# main1.net
KiCad netlist of a schematic drawn in EAGLE
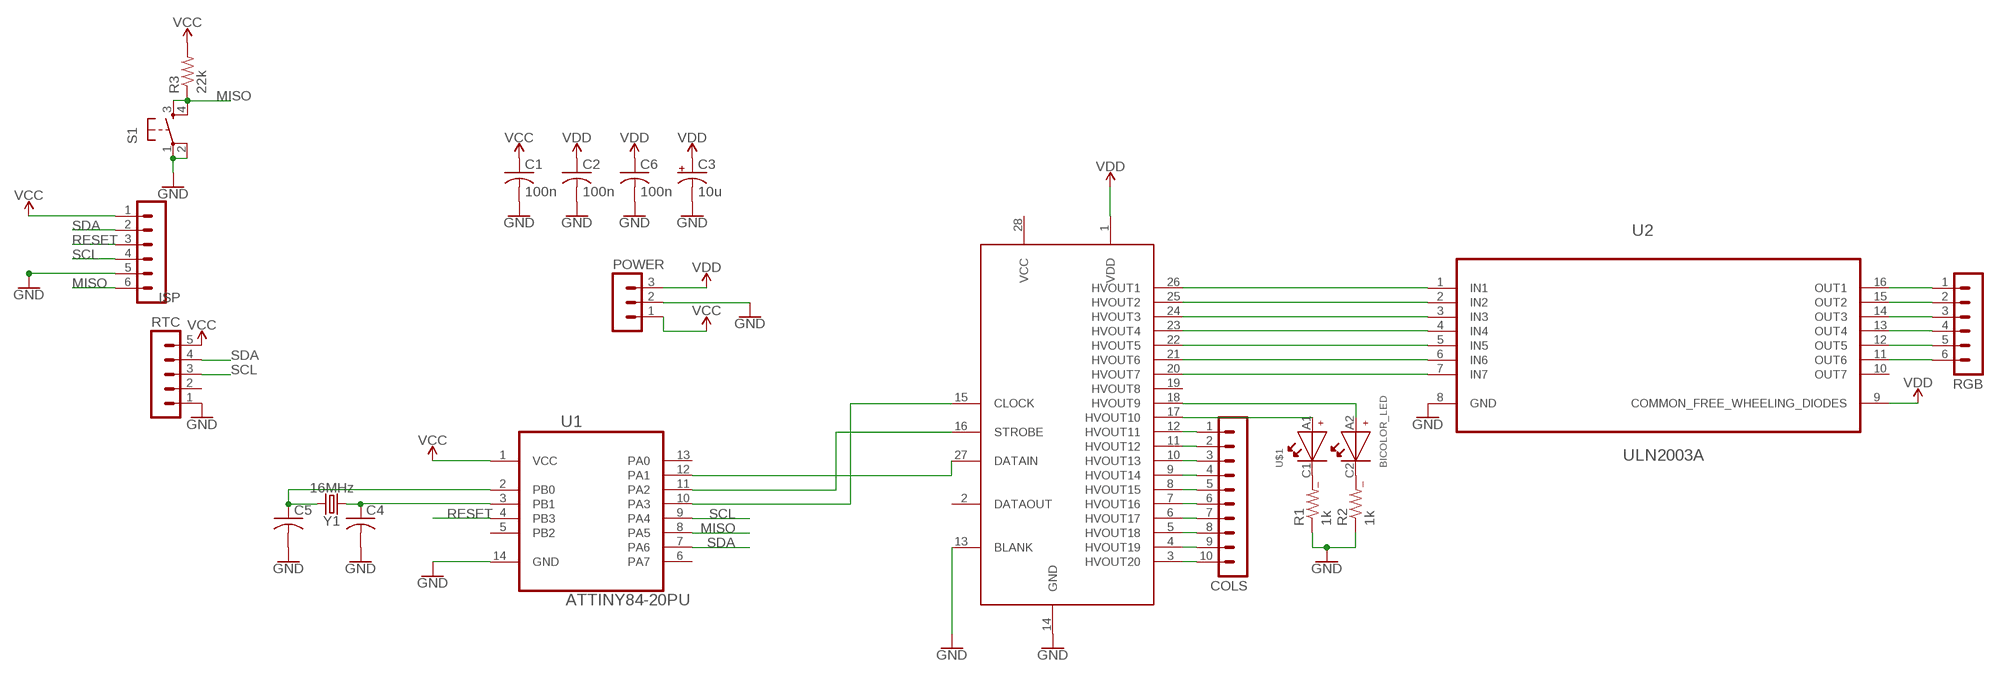
[diagram p0: schematic, sheet 1]

(export (version "E")
  (design (tool "Eeschema 10.0.6"))
  (components
    (comp (ref "C1")
      (value "100n")
      (footprint "eagle-import:C025-025X050")
      (libsource (lib "eagle-import") (part "C-US025-025X050"))
    )
    (comp (ref "C2")
      (value "100n")
      (footprint "eagle-import:C025-025X050")
      (libsource (lib "eagle-import") (part "C-US025-025X050"))
    )
    (comp (ref "C3")
      (value "10u")
      (footprint "eagle-import:E2-5")
      (libsource (lib "eagle-import") (part "CPOL-USE2-5"))
    )
    (comp (ref "C4")
      (value "C-USC0603K")
      (footprint "eagle-import:C0603K")
      (libsource (lib "eagle-import") (part "C-USC0603K"))
    )
    (comp (ref "C5")
      (value "C-USC0603K")
      (footprint "eagle-import:C0603K")
      (libsource (lib "eagle-import") (part "C-USC0603K"))
    )
    (comp (ref "C6")
      (value "100n")
      (footprint "eagle-import:C025-025X050")
      (libsource (lib "eagle-import") (part "C-US025-025X050"))
    )
    (comp (ref "COLS")
      (value "MA10-1W")
      (footprint "eagle-import:MA10-1W")
      (libsource (lib "eagle-import") (part "MA10-1W"))
    )
    (comp (ref "ISP")
      (value "MA06-1")
      (footprint "eagle-import:MA06-1")
      (libsource (lib "eagle-import") (part "MA06-1"))
    )
    (comp (ref "POWER")
      (value "MA03-1")
      (footprint "eagle-import:MA03-1")
      (libsource (lib "eagle-import") (part "MA03-1"))
    )
    (comp (ref "R1")
      (value "1k")
      (footprint "eagle-import:R0603")
      (libsource (lib "eagle-import") (part "R-US_R0603"))
    )
    (comp (ref "R2")
      (value "1k")
      (footprint "eagle-import:R0603")
      (libsource (lib "eagle-import") (part "R-US_R0603"))
    )
    (comp (ref "R3")
      (value "22k")
      (footprint "eagle-import:R0603")
      (libsource (lib "eagle-import") (part "R-US_R0603"))
    )
    (comp (ref "RGB")
      (value "MA06-1")
      (footprint "eagle-import:MA06-1")
      (libsource (lib "eagle-import") (part "MA06-1"))
    )
    (comp (ref "RTC")
      (value "MA05-1")
      (footprint "eagle-import:MA05-1")
      (libsource (lib "eagle-import") (part "MA05-1"))
    )
    (comp (ref "S1")
      (value "TAC_SWITCHPTH")
      (footprint "eagle-import:TACTILE-PTH")
      (libsource (lib "eagle-import") (part "TAC_SWITCHPTH"))
    )
    (comp (ref "U$1")
      (value "BICOLOR_LED")
      (footprint "eagle-import:BICOLOR_LED")
      (libsource (lib "eagle-import") (part "BICOLOR_LED"))
    )
    (comp (ref "U$2")
      (value "HV5812")
      (footprint "eagle-import:DIP254P1524X482-28")
      (libsource (lib "eagle-import") (part "HV5812"))
    )
    (comp (ref "U1")
      (value "ATTINY84-20PU")
      (footprint "eagle-import:DIP254P762X533-14")
      (libsource (lib "eagle-import") (part "ATTINY84-20PU"))
    )
    (comp (ref "U2")
      (value "ULN2003A")
      (footprint "eagle-import:DIP254P762X508-16")
      (libsource (lib "eagle-import") (part "ULN2003A"))
    )
    (comp (ref "Y1")
      (value "16MHz")
      (footprint "eagle-import:HC49US")
      (libsource (lib "eagle-import") (part "CRYSTAL-16MHZPTH-HC49US"))
    )
  )
  (nets
    (net (code "1") (name "/MISO") (class "Default")
      (node (ref "ISP") (pin "6") (pinfunction "6_6") (pintype "passive"))
      (node (ref "R3") (pin "1") (pinfunction "1_1") (pintype "passive"))
      (node (ref "S1") (pin "3") (pinfunction "3_3") (pintype "passive"))
      (node (ref "S1") (pin "4") (pinfunction "4_4") (pintype "passive"))
      (node (ref "U1") (pin "8") (pinfunction "PA5_8") (pintype "bidirectional"))
    )
    (net (code "2") (name "/RESET") (class "Default")
      (node (ref "ISP") (pin "3") (pinfunction "3_3") (pintype "passive"))
      (node (ref "U1") (pin "4") (pinfunction "PB3_4") (pintype "bidirectional"))
    )
    (net (code "3") (name "/SCL") (class "Default")
      (node (ref "ISP") (pin "4") (pinfunction "4_4") (pintype "passive"))
      (node (ref "RTC") (pin "3") (pinfunction "3_3") (pintype "passive"))
      (node (ref "U1") (pin "9") (pinfunction "PA4_9") (pintype "bidirectional"))
    )
    (net (code "4") (name "/SDA") (class "Default")
      (node (ref "ISP") (pin "2") (pinfunction "2_2") (pintype "passive"))
      (node (ref "RTC") (pin "4") (pinfunction "4_4") (pintype "passive"))
      (node (ref "U1") (pin "7") (pinfunction "PA6_7") (pintype "bidirectional"))
    )
    (net (code "5") (name "GND") (class "Default")
      (node (ref "C1") (pin "2") (pinfunction "2_2") (pintype "passive"))
      (node (ref "C2") (pin "2") (pinfunction "2_2") (pintype "passive"))
      (node (ref "C3") (pin "-") (pinfunction "-_-") (pintype "passive"))
      (node (ref "C4") (pin "2") (pinfunction "2_2") (pintype "passive"))
      (node (ref "C5") (pin "2") (pinfunction "2_2") (pintype "passive"))
      (node (ref "C6") (pin "2") (pinfunction "2_2") (pintype "passive"))
      (node (ref "ISP") (pin "5") (pinfunction "5_5") (pintype "passive"))
      (node (ref "POWER") (pin "2") (pinfunction "2_2") (pintype "passive"))
      (node (ref "R1") (pin "1") (pinfunction "1_1") (pintype "passive"))
      (node (ref "R2") (pin "1") (pinfunction "1_1") (pintype "passive"))
      (node (ref "RTC") (pin "1") (pinfunction "1_1") (pintype "passive"))
      (node (ref "S1") (pin "1") (pinfunction "1_1") (pintype "passive"))
      (node (ref "S1") (pin "2") (pinfunction "2_2") (pintype "passive"))
      (node (ref "U$2") (pin "13") (pinfunction "BLANK_13") (pintype "bidirectional"))
      (node (ref "U$2") (pin "14") (pinfunction "GND_14") (pintype "bidirectional"))
      (node (ref "U1") (pin "14") (pinfunction "GND_14") (pintype "passive"))
      (node (ref "U2") (pin "8") (pinfunction "GND_8") (pintype "passive"))
    )
    (net (code "6") (name "Net-(R1-Pad2)") (class "Default")
      (node (ref "R1") (pin "2") (pinfunction "2_2") (pintype "passive"))
      (node (ref "U$1") (pin "C1") (pinfunction "C1_C1") (pintype "passive"))
    )
    (net (code "7") (name "Net-(R2-Pad2)") (class "Default")
      (node (ref "R2") (pin "2") (pinfunction "2_2") (pintype "passive"))
      (node (ref "U$1") (pin "C2") (pinfunction "C2_C2") (pintype "passive"))
    )
    (net (code "8") (name "Net-(U$2-CLOCK)") (class "Default")
      (node (ref "U$2") (pin "15") (pinfunction "CLOCK_15") (pintype "bidirectional"))
      (node (ref "U1") (pin "10") (pinfunction "PA3_10") (pintype "bidirectional"))
    )
    (net (code "9") (name "Net-(U$2-DATAIN)") (class "Default")
      (node (ref "U$2") (pin "27") (pinfunction "DATAIN_27") (pintype "bidirectional"))
      (node (ref "U1") (pin "12") (pinfunction "PA1_12") (pintype "bidirectional"))
    )
    (net (code "10") (name "Net-(U$2-HVOUT1)") (class "Default")
      (node (ref "U$2") (pin "26") (pinfunction "HVOUT1_26") (pintype "bidirectional"))
      (node (ref "U2") (pin "1") (pinfunction "IN1_1") (pintype "input"))
    )
    (net (code "11") (name "Net-(U$2-HVOUT2)") (class "Default")
      (node (ref "U$2") (pin "25") (pinfunction "HVOUT2_25") (pintype "bidirectional"))
      (node (ref "U2") (pin "2") (pinfunction "IN2_2") (pintype "input"))
    )
    (net (code "12") (name "Net-(U$2-HVOUT3)") (class "Default")
      (node (ref "U$2") (pin "24") (pinfunction "HVOUT3_24") (pintype "bidirectional"))
      (node (ref "U2") (pin "3") (pinfunction "IN3_3") (pintype "input"))
    )
    (net (code "13") (name "Net-(U$2-HVOUT4)") (class "Default")
      (node (ref "U$2") (pin "23") (pinfunction "HVOUT4_23") (pintype "bidirectional"))
      (node (ref "U2") (pin "4") (pinfunction "IN4_4") (pintype "input"))
    )
    (net (code "14") (name "Net-(U$2-HVOUT5)") (class "Default")
      (node (ref "U$2") (pin "22") (pinfunction "HVOUT5_22") (pintype "bidirectional"))
      (node (ref "U2") (pin "5") (pinfunction "IN5_5") (pintype "input"))
    )
    (net (code "15") (name "Net-(U$2-HVOUT6)") (class "Default")
      (node (ref "U$2") (pin "21") (pinfunction "HVOUT6_21") (pintype "bidirectional"))
      (node (ref "U2") (pin "6") (pinfunction "IN6_6") (pintype "input"))
    )
    (net (code "16") (name "Net-(U$2-HVOUT7)") (class "Default")
      (node (ref "U$2") (pin "20") (pinfunction "HVOUT7_20") (pintype "bidirectional"))
      (node (ref "U2") (pin "7") (pinfunction "IN7_7") (pintype "input"))
    )
    (net (code "17") (name "Net-(U$2-HVOUT9)") (class "Default")
      (node (ref "U$1") (pin "A2") (pinfunction "A2_A2") (pintype "passive"))
      (node (ref "U$2") (pin "18") (pinfunction "HVOUT9_18") (pintype "bidirectional"))
    )
    (net (code "18") (name "Net-(U$2-HVOUT10)") (class "Default")
      (node (ref "U$1") (pin "A1") (pinfunction "A1_A1") (pintype "passive"))
      (node (ref "U$2") (pin "17") (pinfunction "HVOUT10_17") (pintype "bidirectional"))
    )
    (net (code "19") (name "Net-(U$2-HVOUT11)") (class "Default")
      (node (ref "COLS") (pin "1") (pinfunction "1_1") (pintype "passive"))
      (node (ref "U$2") (pin "12") (pinfunction "HVOUT11_12") (pintype "bidirectional"))
    )
    (net (code "20") (name "Net-(U$2-HVOUT12)") (class "Default")
      (node (ref "COLS") (pin "2") (pinfunction "2_2") (pintype "passive"))
      (node (ref "U$2") (pin "11") (pinfunction "HVOUT12_11") (pintype "bidirectional"))
    )
    (net (code "21") (name "Net-(U$2-HVOUT13)") (class "Default")
      (node (ref "COLS") (pin "3") (pinfunction "3_3") (pintype "passive"))
      (node (ref "U$2") (pin "10") (pinfunction "HVOUT13_10") (pintype "bidirectional"))
    )
    (net (code "22") (name "Net-(U$2-HVOUT14)") (class "Default")
      (node (ref "COLS") (pin "4") (pinfunction "4_4") (pintype "passive"))
      (node (ref "U$2") (pin "9") (pinfunction "HVOUT14_9") (pintype "bidirectional"))
    )
    (net (code "23") (name "Net-(U$2-HVOUT15)") (class "Default")
      (node (ref "COLS") (pin "5") (pinfunction "5_5") (pintype "passive"))
      (node (ref "U$2") (pin "8") (pinfunction "HVOUT15_8") (pintype "bidirectional"))
    )
    (net (code "24") (name "Net-(U$2-HVOUT16)") (class "Default")
      (node (ref "COLS") (pin "6") (pinfunction "6_6") (pintype "passive"))
      (node (ref "U$2") (pin "7") (pinfunction "HVOUT16_7") (pintype "bidirectional"))
    )
    (net (code "25") (name "Net-(U$2-HVOUT17)") (class "Default")
      (node (ref "COLS") (pin "7") (pinfunction "7_7") (pintype "passive"))
      (node (ref "U$2") (pin "6") (pinfunction "HVOUT17_6") (pintype "bidirectional"))
    )
    (net (code "26") (name "Net-(U$2-HVOUT18)") (class "Default")
      (node (ref "COLS") (pin "8") (pinfunction "8_8") (pintype "passive"))
      (node (ref "U$2") (pin "5") (pinfunction "HVOUT18_5") (pintype "bidirectional"))
    )
    (net (code "27") (name "Net-(U$2-HVOUT19)") (class "Default")
      (node (ref "COLS") (pin "9") (pinfunction "9_9") (pintype "passive"))
      (node (ref "U$2") (pin "4") (pinfunction "HVOUT19_4") (pintype "bidirectional"))
    )
    (net (code "28") (name "Net-(U$2-HVOUT20)") (class "Default")
      (node (ref "COLS") (pin "10") (pinfunction "10_10") (pintype "passive"))
      (node (ref "U$2") (pin "3") (pinfunction "HVOUT20_3") (pintype "bidirectional"))
    )
    (net (code "29") (name "Net-(U$2-STROBE)") (class "Default")
      (node (ref "U$2") (pin "16") (pinfunction "STROBE_16") (pintype "bidirectional"))
      (node (ref "U1") (pin "11") (pinfunction "PA2_11") (pintype "bidirectional"))
    )
    (net (code "30") (name "Net-(U1-PB0)") (class "Default")
      (node (ref "C5") (pin "1") (pinfunction "1_1") (pintype "passive"))
      (node (ref "U1") (pin "2") (pinfunction "PB0_2") (pintype "bidirectional"))
      (node (ref "Y1") (pin "2") (pinfunction "2_2") (pintype "passive"))
    )
    (net (code "31") (name "Net-(U1-PB1)") (class "Default")
      (node (ref "C4") (pin "1") (pinfunction "1_1") (pintype "passive"))
      (node (ref "U1") (pin "3") (pinfunction "PB1_3") (pintype "bidirectional"))
      (node (ref "Y1") (pin "1") (pinfunction "1_1") (pintype "passive"))
    )
    (net (code "32") (name "Net-(U2-OUT1)") (class "Default")
      (node (ref "RGB") (pin "1") (pinfunction "1_1") (pintype "passive"))
      (node (ref "U2") (pin "16") (pinfunction "OUT1_16") (pintype "output"))
    )
    (net (code "33") (name "Net-(U2-OUT2)") (class "Default")
      (node (ref "RGB") (pin "2") (pinfunction "2_2") (pintype "passive"))
      (node (ref "U2") (pin "15") (pinfunction "OUT2_15") (pintype "output"))
    )
    (net (code "34") (name "Net-(U2-OUT3)") (class "Default")
      (node (ref "RGB") (pin "3") (pinfunction "3_3") (pintype "passive"))
      (node (ref "U2") (pin "14") (pinfunction "OUT3_14") (pintype "output"))
    )
    (net (code "35") (name "Net-(U2-OUT4)") (class "Default")
      (node (ref "RGB") (pin "4") (pinfunction "4_4") (pintype "passive"))
      (node (ref "U2") (pin "13") (pinfunction "OUT4_13") (pintype "output"))
    )
    (net (code "36") (name "Net-(U2-OUT5)") (class "Default")
      (node (ref "RGB") (pin "5") (pinfunction "5_5") (pintype "passive"))
      (node (ref "U2") (pin "12") (pinfunction "OUT5_12") (pintype "output"))
    )
    (net (code "37") (name "Net-(U2-OUT6)") (class "Default")
      (node (ref "RGB") (pin "6") (pinfunction "6_6") (pintype "passive"))
      (node (ref "U2") (pin "11") (pinfunction "OUT6_11") (pintype "output"))
    )
    (net (code "38") (name "VCC") (class "Default")
      (node (ref "C1") (pin "1") (pinfunction "1_1") (pintype "passive"))
      (node (ref "ISP") (pin "1") (pinfunction "1_1") (pintype "passive"))
      (node (ref "POWER") (pin "1") (pinfunction "1_1") (pintype "passive"))
      (node (ref "R3") (pin "2") (pinfunction "2_2") (pintype "passive"))
      (node (ref "RTC") (pin "5") (pinfunction "5_5") (pintype "passive"))
      (node (ref "U1") (pin "1") (pinfunction "VCC_1") (pintype "power_in"))
    )
    (net (code "39") (name "VDD") (class "Default")
      (node (ref "C2") (pin "1") (pinfunction "1_1") (pintype "passive"))
      (node (ref "C3") (pin "+") (pinfunction "+_+") (pintype "passive"))
      (node (ref "C6") (pin "1") (pinfunction "1_1") (pintype "passive"))
      (node (ref "POWER") (pin "3") (pinfunction "3_3") (pintype "passive"))
      (node (ref "U$2") (pin "1") (pinfunction "VDD_1") (pintype "bidirectional"))
      (node (ref "U2") (pin "9") (pinfunction "COMMON_FREE_WHEELING_DIODES_9") (pintype "passive"))
    )
    (net (code "40") (name "unconnected-(RTC-Pad2)") (class "Default")
      (node (ref "RTC") (pin "2") (pinfunction "2_2") (pintype "passive"))
    )
    (net (code "41") (name "unconnected-(U$2-DATAOUT-Pad2)") (class "Default")
      (node (ref "U$2") (pin "2") (pinfunction "DATAOUT_2") (pintype "bidirectional"))
    )
    (net (code "42") (name "unconnected-(U$2-HVOUT8-Pad19)") (class "Default")
      (node (ref "U$2") (pin "19") (pinfunction "HVOUT8_19") (pintype "bidirectional"))
    )
    (net (code "43") (name "unconnected-(U$2-VCC-Pad28)") (class "Default")
      (node (ref "U$2") (pin "28") (pinfunction "VCC_28") (pintype "bidirectional"))
    )
    (net (code "44") (name "unconnected-(U1-PA0-Pad13)") (class "Default")
      (node (ref "U1") (pin "13") (pinfunction "PA0_13") (pintype "bidirectional"))
    )
    (net (code "45") (name "unconnected-(U1-PA7-Pad6)") (class "Default")
      (node (ref "U1") (pin "6") (pinfunction "PA7_6") (pintype "bidirectional"))
    )
    (net (code "46") (name "unconnected-(U1-PB2-Pad5)") (class "Default")
      (node (ref "U1") (pin "5") (pinfunction "PB2_5") (pintype "bidirectional"))
    )
    (net (code "47") (name "unconnected-(U2-OUT7-Pad10)") (class "Default")
      (node (ref "U2") (pin "10") (pinfunction "OUT7_10") (pintype "output"))
    )
  )
)
